# lm3410-boost-flashlight-driver-17mm-mk-1.net
KiCad netlist of a schematic drawn in EAGLE
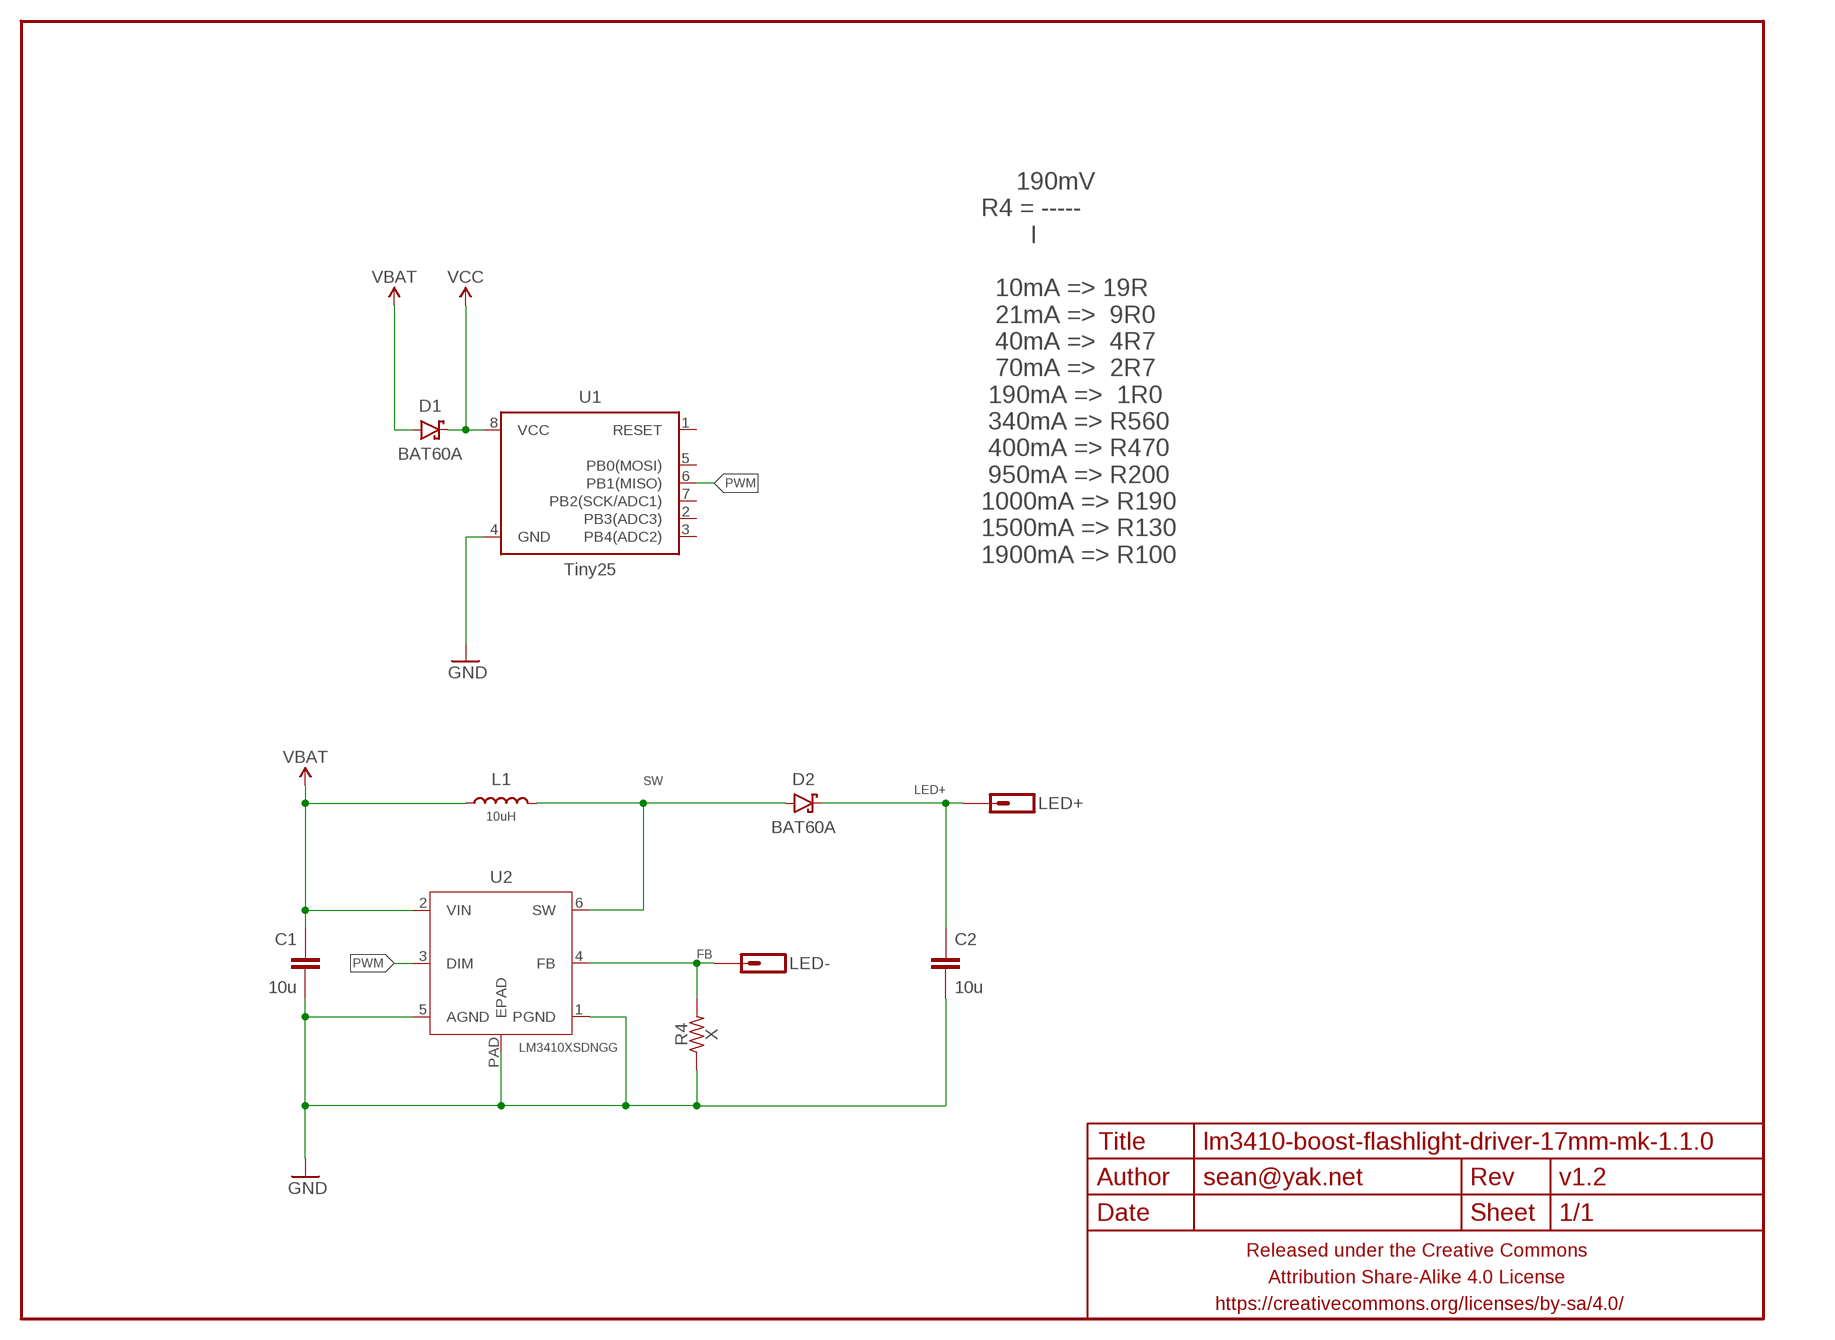
[diagram p0: schematic, sheet 1]

(export (version "E")
  (design (tool "Eeschema 10.0.6"))
  (components
    (comp (ref "C1")
      (value "10u")
      (footprint "eagle-import:C0805-TIGHTER")
      (libsource (lib "eagle-import") (part "CAPACITOR-CERAMICC0805-TIGHTER"))
    )
    (comp (ref "C2")
      (value "10u")
      (footprint "eagle-import:C0805-TIGHTER")
      (libsource (lib "eagle-import") (part "CAPACITOR-CERAMICC0805-TIGHTER"))
    )
    (comp (ref "D1")
      (value "BAT60A")
      (footprint "eagle-import:SOD323-SCHOTTKY")
      (libsource (lib "eagle-import") (part "DIODE-SCHOTTKYSOD323"))
    )
    (comp (ref "D2")
      (value "BAT60A")
      (footprint "eagle-import:SOD323-SCHOTTKY")
      (libsource (lib "eagle-import") (part "DIODE-SCHOTTKYSOD323"))
    )
    (comp (ref "FRAME1")
      (value "FRAME-LETTERNO_PACKAGE")
      (footprint "eagle-import:DUMMY")
      (fields (field (name "DESIGNER") "sean@yak.net") (field (name "VERSION") "v1.2"))
      (libsource (lib "eagle-import") (part "FRAME-LETTERNO_PACKAGE"))
    )
    (comp (ref "L1")
      (value "10uH")
      (footprint "eagle-import:XFL4020")
      (libsource (lib "eagle-import") (part "INDUCTORXFL4020"))
    )
    (comp (ref "LED+")
      (value "M01PTH-1MM-CIR-NS")
      (footprint "eagle-import:1X01-1MM-CIR-NS")
      (libsource (lib "eagle-import") (part "M01PTH-1MM-CIR-NS"))
    )
    (comp (ref "LED-")
      (value "M01PTH-1MM-CIR-NS")
      (footprint "eagle-import:1X01-1MM-CIR-NS")
      (libsource (lib "eagle-import") (part "M01PTH-1MM-CIR-NS"))
    )
    (comp (ref "R4")
      (value "X")
      (footprint "eagle-import:R0805-TIGHTER")
      (libsource (lib "eagle-import") (part "RESISTORR0805-TIGHTER"))
    )
    (comp (ref "U1")
      (value "Tiny25")
      (footprint "eagle-import:SO08-SKINNYPADS")
      (libsource (lib "eagle-import") (part "ATTINY45TINY25-SOICN-NARROWER"))
    )
    (comp (ref "U2")
      (value "LM3410XSDNGG")
      (footprint "eagle-import:DFN300X300X80-7N")
      (fields (field (name "MPN") "LM3410XSD"))
      (libsource (lib "eagle-import") (part "LM3410XSDNGG"))
    )
  )
  (nets
    (net (code "1") (name "/FB") (class "Default")
      (node (ref "LED-") (pin "1") (pinfunction "1_1") (pintype "passive"))
      (node (ref "R4") (pin "2") (pinfunction "2_2") (pintype "passive"))
      (node (ref "U2") (pin "4") (pinfunction "FB_4") (pintype "input"))
    )
    (net (code "2") (name "/LED+") (class "Default")
      (node (ref "C2") (pin "1") (pinfunction "1_1") (pintype "passive"))
      (node (ref "D2") (pin "C") (pinfunction "C_C") (pintype "passive"))
      (node (ref "LED+") (pin "1") (pinfunction "1_1") (pintype "passive"))
    )
    (net (code "3") (name "/SW") (class "Default")
      (node (ref "D2") (pin "A") (pinfunction "A_A") (pintype "passive"))
      (node (ref "L1") (pin "P$2") (pinfunction "2_P$2") (pintype "passive"))
      (node (ref "U2") (pin "6") (pinfunction "SW_6") (pintype "output"))
    )
    (net (code "4") (name "GND") (class "Default")
      (node (ref "C1") (pin "2") (pinfunction "2_2") (pintype "passive"))
      (node (ref "C2") (pin "2") (pinfunction "2_2") (pintype "passive"))
      (node (ref "R4") (pin "1") (pinfunction "1_1") (pintype "passive"))
      (node (ref "U1") (pin "4") (pinfunction "GND_4") (pintype "bidirectional"))
      (node (ref "U2") (pin "1") (pinfunction "PGND_1") (pintype "passive"))
      (node (ref "U2") (pin "5") (pinfunction "AGND_5") (pintype "passive"))
      (node (ref "U2") (pin "PAD") (pinfunction "EPAD_PAD") (pintype "passive"))
    )
    (net (code "5") (name "PWM") (class "Default")
      (node (ref "U1") (pin "6") (pinfunction "PB1(MISO)_6") (pintype "bidirectional"))
      (node (ref "U2") (pin "3") (pinfunction "DIM_3") (pintype "input"))
    )
    (net (code "6") (name "VBAT") (class "Default")
      (node (ref "C1") (pin "1") (pinfunction "1_1") (pintype "passive"))
      (node (ref "D1") (pin "A") (pinfunction "A_A") (pintype "passive"))
      (node (ref "L1") (pin "P$1") (pinfunction "1_P$1") (pintype "passive"))
      (node (ref "U2") (pin "2") (pinfunction "VIN_2") (pintype "power_in"))
    )
    (net (code "7") (name "VCC") (class "Default")
      (node (ref "D1") (pin "C") (pinfunction "C_C") (pintype "passive"))
      (node (ref "U1") (pin "8") (pinfunction "VCC_8") (pintype "bidirectional"))
    )
    (net (code "8") (name "unconnected-(U1-PB0(MOSI)-Pad5)") (class "Default")
      (node (ref "U1") (pin "5") (pinfunction "PB0(MOSI)_5") (pintype "bidirectional"))
    )
    (net (code "9") (name "unconnected-(U1-PB2(SCK{slash}ADC1)-Pad7)") (class "Default")
      (node (ref "U1") (pin "7") (pinfunction "PB2(SCK/ADC1)_7") (pintype "bidirectional"))
    )
    (net (code "10") (name "unconnected-(U1-PB3(ADC3)-Pad2)") (class "Default")
      (node (ref "U1") (pin "2") (pinfunction "PB3(ADC3)_2") (pintype "bidirectional"))
    )
    (net (code "11") (name "unconnected-(U1-PB4(ADC2)-Pad3)") (class "Default")
      (node (ref "U1") (pin "3") (pinfunction "PB4(ADC2)_3") (pintype "bidirectional"))
    )
    (net (code "12") (name "unconnected-(U1-RESET-Pad1)") (class "Default")
      (node (ref "U1") (pin "1") (pinfunction "RESET_1") (pintype "bidirectional"))
    )
  )
)
